# motor_shield.net
KiCad netlist of a schematic drawn in EAGLE
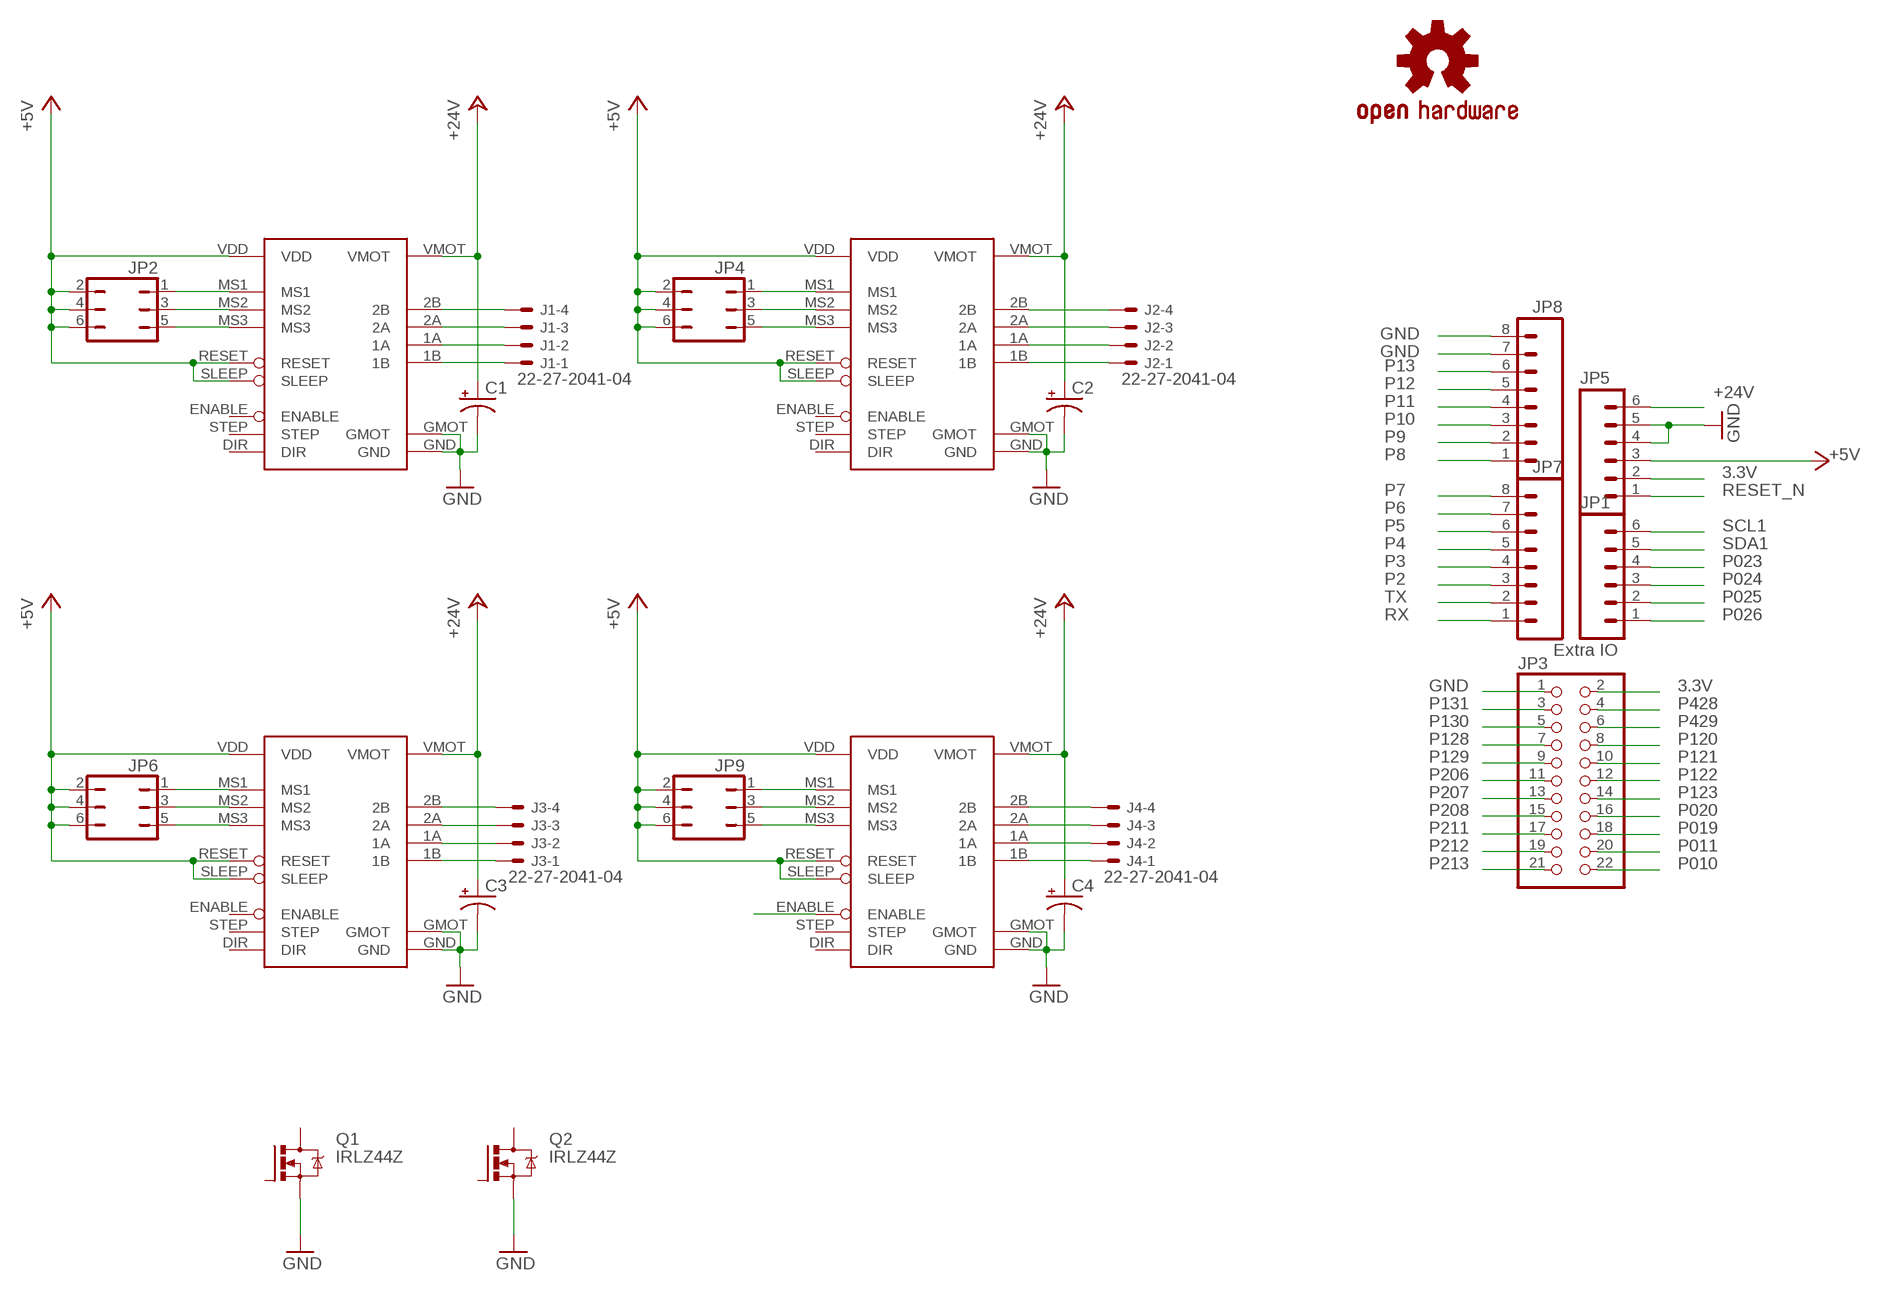
[diagram p0: schematic, sheet 1]

(export (version "E")
  (design (tool "Eeschema 10.0.6"))
  (components
    (comp (ref "C1")
      (value "CAP_POLPTH1")
      (footprint "eagle-import:CPOL-RADIAL-100UF-25V")
      (libsource (lib "eagle-import") (part "CAP_POLPTH1"))
    )
    (comp (ref "C2")
      (value "CAP_POLPTH1")
      (footprint "eagle-import:CPOL-RADIAL-100UF-25V")
      (libsource (lib "eagle-import") (part "CAP_POLPTH1"))
    )
    (comp (ref "C3")
      (value "CAP_POLPTH1")
      (footprint "eagle-import:CPOL-RADIAL-100UF-25V")
      (libsource (lib "eagle-import") (part "CAP_POLPTH1"))
    )
    (comp (ref "C4")
      (value "CAP_POLPTH1")
      (footprint "eagle-import:CPOL-RADIAL-100UF-25V")
      (libsource (lib "eagle-import") (part "CAP_POLPTH1"))
    )
    (comp (ref "J1")
      (value "22-27-2041-04")
      (footprint "eagle-import:6410-04")
      (libsource (lib "eagle-import") (part "22-?-0427-2041"))
    )
    (comp (ref "J2")
      (value "22-27-2041-04")
      (footprint "eagle-import:6410-04")
      (libsource (lib "eagle-import") (part "22-?-0427-2041"))
    )
    (comp (ref "J3")
      (value "22-27-2041-04")
      (footprint "eagle-import:6410-04")
      (libsource (lib "eagle-import") (part "22-?-0427-2041"))
    )
    (comp (ref "J4")
      (value "22-27-2041-04")
      (footprint "eagle-import:6410-04")
      (libsource (lib "eagle-import") (part "22-?-0427-2041"))
    )
    (comp (ref "JP1")
      (value "M06SIP")
      (footprint "eagle-import:1X06")
      (libsource (lib "eagle-import") (part "M06SIP"))
    )
    (comp (ref "JP2")
      (value "JP3Q")
      (footprint "eagle-import:JP3Q")
      (libsource (lib "eagle-import") (part "JP3Q"))
    )
    (comp (ref "JP3")
      (value "PINHD-2X11")
      (footprint "eagle-import:2X11")
      (libsource (lib "eagle-import") (part "PINHD-2X11"))
    )
    (comp (ref "JP4")
      (value "JP3Q")
      (footprint "eagle-import:JP3Q")
      (libsource (lib "eagle-import") (part "JP3Q"))
    )
    (comp (ref "JP5")
      (value "M06SIP")
      (footprint "eagle-import:1X06")
      (libsource (lib "eagle-import") (part "M06SIP"))
    )
    (comp (ref "JP6")
      (value "JP3Q")
      (footprint "eagle-import:JP3Q")
      (libsource (lib "eagle-import") (part "JP3Q"))
    )
    (comp (ref "JP7")
      (value "M08")
      (footprint "eagle-import:1X08")
      (libsource (lib "eagle-import") (part "M08"))
    )
    (comp (ref "JP8")
      (value "M08")
      (footprint "eagle-import:1X08")
      (libsource (lib "eagle-import") (part "M08"))
    )
    (comp (ref "JP9")
      (value "JP3Q")
      (footprint "eagle-import:JP3Q")
      (libsource (lib "eagle-import") (part "JP3Q"))
    )
    (comp (ref "OPENHARDWARE")
      (value "OSHW-LOGOL")
      (footprint "eagle-import:OSHW-LOGO-L")
      (libsource (lib "eagle-import") (part "OSHW-LOGOL"))
    )
    (comp (ref "Q1")
      (value "IRLZ44Z")
      (footprint "eagle-import:TO220BH")
      (libsource (lib "eagle-import") (part "IRLZ44Z"))
    )
    (comp (ref "Q2")
      (value "IRLZ44Z")
      (footprint "eagle-import:TO220BH")
      (libsource (lib "eagle-import") (part "IRLZ44Z"))
    )
    (comp (ref "U$1")
      (value "A4988")
      (footprint "eagle-import:A4988")
      (libsource (lib "eagle-import") (part "A4988"))
    )
    (comp (ref "U$2")
      (value "A4988")
      (footprint "eagle-import:A4988")
      (libsource (lib "eagle-import") (part "A4988"))
    )
    (comp (ref "U$3")
      (value "A4988")
      (footprint "eagle-import:A4988")
      (libsource (lib "eagle-import") (part "A4988"))
    )
    (comp (ref "U$4")
      (value "A4988")
      (footprint "eagle-import:A4988")
      (libsource (lib "eagle-import") (part "A4988"))
    )
  )
  (nets
    (net (code "1") (name "+5V") (class "Default")
      (node (ref "JP2") (pin "2") (pinfunction "2_2") (pintype "passive"))
      (node (ref "JP2") (pin "4") (pinfunction "4_4") (pintype "passive"))
      (node (ref "JP2") (pin "6") (pinfunction "6_6") (pintype "passive"))
      (node (ref "JP4") (pin "2") (pinfunction "2_2") (pintype "passive"))
      (node (ref "JP4") (pin "4") (pinfunction "4_4") (pintype "passive"))
      (node (ref "JP4") (pin "6") (pinfunction "6_6") (pintype "passive"))
      (node (ref "JP5") (pin "3") (pinfunction "3_3") (pintype "passive"))
      (node (ref "JP6") (pin "2") (pinfunction "2_2") (pintype "passive"))
      (node (ref "JP6") (pin "4") (pinfunction "4_4") (pintype "passive"))
      (node (ref "JP6") (pin "6") (pinfunction "6_6") (pintype "passive"))
      (node (ref "JP9") (pin "2") (pinfunction "2_2") (pintype "passive"))
      (node (ref "JP9") (pin "4") (pinfunction "4_4") (pintype "passive"))
      (node (ref "JP9") (pin "6") (pinfunction "6_6") (pintype "passive"))
      (node (ref "U$1") (pin "RESET") (pinfunction "RESET_RESET") (pintype "input"))
      (node (ref "U$1") (pin "SLEEP") (pinfunction "SLEEP_SLEEP") (pintype "input"))
      (node (ref "U$1") (pin "VDD") (pinfunction "VDD_VDD") (pintype "bidirectional"))
      (node (ref "U$2") (pin "RESET") (pinfunction "RESET_RESET") (pintype "input"))
      (node (ref "U$2") (pin "SLEEP") (pinfunction "SLEEP_SLEEP") (pintype "input"))
      (node (ref "U$2") (pin "VDD") (pinfunction "VDD_VDD") (pintype "bidirectional"))
      (node (ref "U$3") (pin "RESET") (pinfunction "RESET_RESET") (pintype "input"))
      (node (ref "U$3") (pin "SLEEP") (pinfunction "SLEEP_SLEEP") (pintype "input"))
      (node (ref "U$3") (pin "VDD") (pinfunction "VDD_VDD") (pintype "bidirectional"))
      (node (ref "U$4") (pin "RESET") (pinfunction "RESET_RESET") (pintype "input"))
      (node (ref "U$4") (pin "SLEEP") (pinfunction "SLEEP_SLEEP") (pintype "input"))
      (node (ref "U$4") (pin "VDD") (pinfunction "VDD_VDD") (pintype "bidirectional"))
    )
    (net (code "2") (name "+24V") (class "Default")
      (node (ref "C1") (pin "1") (pinfunction "+_1") (pintype "passive"))
      (node (ref "C2") (pin "1") (pinfunction "+_1") (pintype "passive"))
      (node (ref "C3") (pin "1") (pinfunction "+_1") (pintype "passive"))
      (node (ref "C4") (pin "1") (pinfunction "+_1") (pintype "passive"))
      (node (ref "JP5") (pin "6") (pinfunction "6_6") (pintype "passive"))
      (node (ref "U$1") (pin "VMOT") (pinfunction "VMOT_VMOT") (pintype "bidirectional"))
      (node (ref "U$2") (pin "VMOT") (pinfunction "VMOT_VMOT") (pintype "bidirectional"))
      (node (ref "U$3") (pin "VMOT") (pinfunction "VMOT_VMOT") (pintype "bidirectional"))
      (node (ref "U$4") (pin "VMOT") (pinfunction "VMOT_VMOT") (pintype "bidirectional"))
    )
    (net (code "3") (name "/3.3V") (class "Default")
      (node (ref "JP3") (pin "2") (pinfunction "2_2") (pintype "passive"))
      (node (ref "JP5") (pin "2") (pinfunction "2_2") (pintype "passive"))
    )
    (net (code "4") (name "/P2") (class "Default")
      (node (ref "JP7") (pin "3") (pinfunction "3_3") (pintype "passive"))
    )
    (net (code "5") (name "/P3") (class "Default")
      (node (ref "JP7") (pin "4") (pinfunction "4_4") (pintype "passive"))
    )
    (net (code "6") (name "/P4") (class "Default")
      (node (ref "JP7") (pin "5") (pinfunction "5_5") (pintype "passive"))
    )
    (net (code "7") (name "/P5") (class "Default")
      (node (ref "JP7") (pin "6") (pinfunction "6_6") (pintype "passive"))
    )
    (net (code "8") (name "/P6") (class "Default")
      (node (ref "JP7") (pin "7") (pinfunction "7_7") (pintype "passive"))
    )
    (net (code "9") (name "/P7") (class "Default")
      (node (ref "JP7") (pin "8") (pinfunction "8_8") (pintype "passive"))
    )
    (net (code "10") (name "/P8") (class "Default")
      (node (ref "JP8") (pin "1") (pinfunction "1_1") (pintype "passive"))
    )
    (net (code "11") (name "/P9") (class "Default")
      (node (ref "JP8") (pin "2") (pinfunction "2_2") (pintype "passive"))
    )
    (net (code "12") (name "/P010") (class "Default")
      (node (ref "JP3") (pin "22") (pinfunction "22_22") (pintype "passive"))
    )
    (net (code "13") (name "/P10") (class "Default")
      (node (ref "JP8") (pin "3") (pinfunction "3_3") (pintype "passive"))
    )
    (net (code "14") (name "/P11") (class "Default")
      (node (ref "JP8") (pin "4") (pinfunction "4_4") (pintype "passive"))
    )
    (net (code "15") (name "/P011") (class "Default")
      (node (ref "JP3") (pin "20") (pinfunction "20_20") (pintype "passive"))
    )
    (net (code "16") (name "/P12") (class "Default")
      (node (ref "JP8") (pin "5") (pinfunction "5_5") (pintype "passive"))
    )
    (net (code "17") (name "/P13") (class "Default")
      (node (ref "JP8") (pin "6") (pinfunction "6_6") (pintype "passive"))
    )
    (net (code "18") (name "/P019") (class "Default")
      (node (ref "JP3") (pin "18") (pinfunction "18_18") (pintype "passive"))
    )
    (net (code "19") (name "/P020") (class "Default")
      (node (ref "JP3") (pin "16") (pinfunction "16_16") (pintype "passive"))
    )
    (net (code "20") (name "/P023") (class "Default")
      (node (ref "JP1") (pin "4") (pinfunction "4_4") (pintype "passive"))
    )
    (net (code "21") (name "/P024") (class "Default")
      (node (ref "JP1") (pin "3") (pinfunction "3_3") (pintype "passive"))
    )
    (net (code "22") (name "/P025") (class "Default")
      (node (ref "JP1") (pin "2") (pinfunction "2_2") (pintype "passive"))
    )
    (net (code "23") (name "/P026") (class "Default")
      (node (ref "JP1") (pin "1") (pinfunction "1_1") (pintype "passive"))
      (node (ref "U$4") (pin "ENABLE") (pinfunction "ENABLE_ENABLE") (pintype "input"))
    )
    (net (code "24") (name "/P120") (class "Default")
      (node (ref "JP3") (pin "8") (pinfunction "8_8") (pintype "passive"))
    )
    (net (code "25") (name "/P121") (class "Default")
      (node (ref "JP3") (pin "10") (pinfunction "10_10") (pintype "passive"))
    )
    (net (code "26") (name "/P122") (class "Default")
      (node (ref "JP3") (pin "12") (pinfunction "12_12") (pintype "passive"))
    )
    (net (code "27") (name "/P123") (class "Default")
      (node (ref "JP3") (pin "14") (pinfunction "14_14") (pintype "passive"))
    )
    (net (code "28") (name "/P128") (class "Default")
      (node (ref "JP3") (pin "7") (pinfunction "7_7") (pintype "passive"))
    )
    (net (code "29") (name "/P129") (class "Default")
      (node (ref "JP3") (pin "9") (pinfunction "9_9") (pintype "passive"))
    )
    (net (code "30") (name "/P130") (class "Default")
      (node (ref "JP3") (pin "5") (pinfunction "5_5") (pintype "passive"))
    )
    (net (code "31") (name "/P131") (class "Default")
      (node (ref "JP3") (pin "3") (pinfunction "3_3") (pintype "passive"))
    )
    (net (code "32") (name "/P206") (class "Default")
      (node (ref "JP3") (pin "11") (pinfunction "11_11") (pintype "passive"))
    )
    (net (code "33") (name "/P207") (class "Default")
      (node (ref "JP3") (pin "13") (pinfunction "13_13") (pintype "passive"))
    )
    (net (code "34") (name "/P208") (class "Default")
      (node (ref "JP3") (pin "15") (pinfunction "15_15") (pintype "passive"))
    )
    (net (code "35") (name "/P211") (class "Default")
      (node (ref "JP3") (pin "17") (pinfunction "17_17") (pintype "passive"))
    )
    (net (code "36") (name "/P212") (class "Default")
      (node (ref "JP3") (pin "19") (pinfunction "19_19") (pintype "passive"))
    )
    (net (code "37") (name "/P213") (class "Default")
      (node (ref "JP3") (pin "21") (pinfunction "21_21") (pintype "passive"))
    )
    (net (code "38") (name "/P428") (class "Default")
      (node (ref "JP3") (pin "4") (pinfunction "4_4") (pintype "passive"))
    )
    (net (code "39") (name "/P429") (class "Default")
      (node (ref "JP3") (pin "6") (pinfunction "6_6") (pintype "passive"))
    )
    (net (code "40") (name "/RESET_N") (class "Default")
      (node (ref "JP5") (pin "1") (pinfunction "1_1") (pintype "passive"))
    )
    (net (code "41") (name "/RX") (class "Default")
      (node (ref "JP7") (pin "1") (pinfunction "1_1") (pintype "passive"))
    )
    (net (code "42") (name "/SCL1") (class "Default")
      (node (ref "JP1") (pin "6") (pinfunction "6_6") (pintype "passive"))
    )
    (net (code "43") (name "/SDA1") (class "Default")
      (node (ref "JP1") (pin "5") (pinfunction "5_5") (pintype "passive"))
    )
    (net (code "44") (name "/TX") (class "Default")
      (node (ref "JP7") (pin "2") (pinfunction "2_2") (pintype "passive"))
    )
    (net (code "45") (name "GND") (class "Default")
      (node (ref "C1") (pin "2") (pinfunction "-_2") (pintype "passive"))
      (node (ref "C2") (pin "2") (pinfunction "-_2") (pintype "passive"))
      (node (ref "C3") (pin "2") (pinfunction "-_2") (pintype "passive"))
      (node (ref "C4") (pin "2") (pinfunction "-_2") (pintype "passive"))
      (node (ref "JP3") (pin "1") (pinfunction "1_1") (pintype "passive"))
      (node (ref "JP5") (pin "4") (pinfunction "4_4") (pintype "passive"))
      (node (ref "JP5") (pin "5") (pinfunction "5_5") (pintype "passive"))
      (node (ref "JP8") (pin "7") (pinfunction "7_7") (pintype "passive"))
      (node (ref "JP8") (pin "8") (pinfunction "8_8") (pintype "passive"))
      (node (ref "Q1") (pin "S") (pinfunction "S_S") (pintype "passive"))
      (node (ref "Q2") (pin "S") (pinfunction "S_S") (pintype "passive"))
      (node (ref "U$1") (pin "GMOT") (pinfunction "GMOT_GMOT") (pintype "bidirectional"))
      (node (ref "U$1") (pin "GND") (pinfunction "GND_GND") (pintype "bidirectional"))
      (node (ref "U$2") (pin "GMOT") (pinfunction "GMOT_GMOT") (pintype "bidirectional"))
      (node (ref "U$2") (pin "GND") (pinfunction "GND_GND") (pintype "bidirectional"))
      (node (ref "U$3") (pin "GMOT") (pinfunction "GMOT_GMOT") (pintype "bidirectional"))
      (node (ref "U$3") (pin "GND") (pinfunction "GND_GND") (pintype "bidirectional"))
      (node (ref "U$4") (pin "GMOT") (pinfunction "GMOT_GMOT") (pintype "bidirectional"))
      (node (ref "U$4") (pin "GND") (pinfunction "GND_GND") (pintype "bidirectional"))
    )
    (net (code "46") (name "Net-(J1A-S)") (class "Default")
      (node (ref "J1") (pin "1") (pinfunction "S_1") (pintype "passive"))
      (node (ref "U$1") (pin "1B") (pinfunction "1B_1B") (pintype "output"))
    )
    (net (code "47") (name "Net-(J1B-S)") (class "Default")
      (node (ref "J1") (pin "2") (pinfunction "S_2") (pintype "passive"))
      (node (ref "U$1") (pin "1A") (pinfunction "1A_1A") (pintype "output"))
    )
    (net (code "48") (name "Net-(J1C-S)") (class "Default")
      (node (ref "J1") (pin "3") (pinfunction "S_3") (pintype "passive"))
      (node (ref "U$1") (pin "2A") (pinfunction "2A_2A") (pintype "output"))
    )
    (net (code "49") (name "Net-(J1D-S)") (class "Default")
      (node (ref "J1") (pin "4") (pinfunction "S_4") (pintype "passive"))
      (node (ref "U$1") (pin "2B") (pinfunction "2B_2B") (pintype "output"))
    )
    (net (code "50") (name "Net-(J2A-S)") (class "Default")
      (node (ref "J2") (pin "1") (pinfunction "S_1") (pintype "passive"))
      (node (ref "U$2") (pin "1B") (pinfunction "1B_1B") (pintype "output"))
    )
    (net (code "51") (name "Net-(J2B-S)") (class "Default")
      (node (ref "J2") (pin "2") (pinfunction "S_2") (pintype "passive"))
      (node (ref "U$2") (pin "1A") (pinfunction "1A_1A") (pintype "output"))
    )
    (net (code "52") (name "Net-(J2C-S)") (class "Default")
      (node (ref "J2") (pin "3") (pinfunction "S_3") (pintype "passive"))
      (node (ref "U$2") (pin "2A") (pinfunction "2A_2A") (pintype "output"))
    )
    (net (code "53") (name "Net-(J2D-S)") (class "Default")
      (node (ref "J2") (pin "4") (pinfunction "S_4") (pintype "passive"))
      (node (ref "U$2") (pin "2B") (pinfunction "2B_2B") (pintype "output"))
    )
    (net (code "54") (name "Net-(J3A-S)") (class "Default")
      (node (ref "J3") (pin "1") (pinfunction "S_1") (pintype "passive"))
      (node (ref "U$3") (pin "1B") (pinfunction "1B_1B") (pintype "output"))
    )
    (net (code "55") (name "Net-(J3B-S)") (class "Default")
      (node (ref "J3") (pin "2") (pinfunction "S_2") (pintype "passive"))
      (node (ref "U$3") (pin "1A") (pinfunction "1A_1A") (pintype "output"))
    )
    (net (code "56") (name "Net-(J3C-S)") (class "Default")
      (node (ref "J3") (pin "3") (pinfunction "S_3") (pintype "passive"))
      (node (ref "U$3") (pin "2A") (pinfunction "2A_2A") (pintype "output"))
    )
    (net (code "57") (name "Net-(J3D-S)") (class "Default")
      (node (ref "J3") (pin "4") (pinfunction "S_4") (pintype "passive"))
      (node (ref "U$3") (pin "2B") (pinfunction "2B_2B") (pintype "output"))
    )
    (net (code "58") (name "Net-(J4A-S)") (class "Default")
      (node (ref "J4") (pin "1") (pinfunction "S_1") (pintype "passive"))
      (node (ref "U$4") (pin "1B") (pinfunction "1B_1B") (pintype "output"))
    )
    (net (code "59") (name "Net-(J4B-S)") (class "Default")
      (node (ref "J4") (pin "2") (pinfunction "S_2") (pintype "passive"))
      (node (ref "U$4") (pin "1A") (pinfunction "1A_1A") (pintype "output"))
    )
    (net (code "60") (name "Net-(J4C-S)") (class "Default")
      (node (ref "J4") (pin "3") (pinfunction "S_3") (pintype "passive"))
      (node (ref "U$4") (pin "2A") (pinfunction "2A_2A") (pintype "output"))
    )
    (net (code "61") (name "Net-(J4D-S)") (class "Default")
      (node (ref "J4") (pin "4") (pinfunction "S_4") (pintype "passive"))
      (node (ref "U$4") (pin "2B") (pinfunction "2B_2B") (pintype "output"))
    )
    (net (code "62") (name "Net-(JP2-Pad1)") (class "Default")
      (node (ref "JP2") (pin "1") (pinfunction "1_1") (pintype "passive"))
      (node (ref "U$1") (pin "MS1") (pinfunction "MS1_MS1") (pintype "bidirectional"))
    )
    (net (code "63") (name "Net-(JP2-Pad3)") (class "Default")
      (node (ref "JP2") (pin "3") (pinfunction "3_3") (pintype "passive"))
      (node (ref "U$1") (pin "MS2") (pinfunction "MS2_MS2") (pintype "bidirectional"))
    )
    (net (code "64") (name "Net-(JP2-Pad5)") (class "Default")
      (node (ref "JP2") (pin "5") (pinfunction "5_5") (pintype "passive"))
      (node (ref "U$1") (pin "MS3") (pinfunction "MS3_MS3") (pintype "bidirectional"))
    )
    (net (code "65") (name "Net-(JP4-Pad1)") (class "Default")
      (node (ref "JP4") (pin "1") (pinfunction "1_1") (pintype "passive"))
      (node (ref "U$2") (pin "MS1") (pinfunction "MS1_MS1") (pintype "bidirectional"))
    )
    (net (code "66") (name "Net-(JP4-Pad3)") (class "Default")
      (node (ref "JP4") (pin "3") (pinfunction "3_3") (pintype "passive"))
      (node (ref "U$2") (pin "MS2") (pinfunction "MS2_MS2") (pintype "bidirectional"))
    )
    (net (code "67") (name "Net-(JP4-Pad5)") (class "Default")
      (node (ref "JP4") (pin "5") (pinfunction "5_5") (pintype "passive"))
      (node (ref "U$2") (pin "MS3") (pinfunction "MS3_MS3") (pintype "bidirectional"))
    )
    (net (code "68") (name "Net-(JP6-Pad1)") (class "Default")
      (node (ref "JP6") (pin "1") (pinfunction "1_1") (pintype "passive"))
      (node (ref "U$3") (pin "MS1") (pinfunction "MS1_MS1") (pintype "bidirectional"))
    )
    (net (code "69") (name "Net-(JP6-Pad3)") (class "Default")
      (node (ref "JP6") (pin "3") (pinfunction "3_3") (pintype "passive"))
      (node (ref "U$3") (pin "MS2") (pinfunction "MS2_MS2") (pintype "bidirectional"))
    )
    (net (code "70") (name "Net-(JP6-Pad5)") (class "Default")
      (node (ref "JP6") (pin "5") (pinfunction "5_5") (pintype "passive"))
      (node (ref "U$3") (pin "MS3") (pinfunction "MS3_MS3") (pintype "bidirectional"))
    )
    (net (code "71") (name "Net-(JP9-Pad1)") (class "Default")
      (node (ref "JP9") (pin "1") (pinfunction "1_1") (pintype "passive"))
      (node (ref "U$4") (pin "MS1") (pinfunction "MS1_MS1") (pintype "bidirectional"))
    )
    (net (code "72") (name "Net-(JP9-Pad3)") (class "Default")
      (node (ref "JP9") (pin "3") (pinfunction "3_3") (pintype "passive"))
      (node (ref "U$4") (pin "MS2") (pinfunction "MS2_MS2") (pintype "bidirectional"))
    )
    (net (code "73") (name "Net-(JP9-Pad5)") (class "Default")
      (node (ref "JP9") (pin "5") (pinfunction "5_5") (pintype "passive"))
      (node (ref "U$4") (pin "MS3") (pinfunction "MS3_MS3") (pintype "bidirectional"))
    )
    (net (code "74") (name "unconnected-(Q1-PadD)") (class "Default")
      (node (ref "Q1") (pin "D") (pinfunction "D_D") (pintype "passive"))
    )
    (net (code "75") (name "unconnected-(Q1-PadG)") (class "Default")
      (node (ref "Q1") (pin "G") (pinfunction "G_G") (pintype "passive"))
    )
    (net (code "76") (name "unconnected-(Q2-PadD)") (class "Default")
      (node (ref "Q2") (pin "D") (pinfunction "D_D") (pintype "passive"))
    )
    (net (code "77") (name "unconnected-(Q2-PadG)") (class "Default")
      (node (ref "Q2") (pin "G") (pinfunction "G_G") (pintype "passive"))
    )
    (net (code "78") (name "unconnected-(U$1-PadDIR)") (class "Default")
      (node (ref "U$1") (pin "DIR") (pinfunction "DIR_DIR") (pintype "input"))
    )
    (net (code "79") (name "unconnected-(U$1-PadENABLE)") (class "Default")
      (node (ref "U$1") (pin "ENABLE") (pinfunction "ENABLE_ENABLE") (pintype "input"))
    )
    (net (code "80") (name "unconnected-(U$1-PadSTEP)") (class "Default")
      (node (ref "U$1") (pin "STEP") (pinfunction "STEP_STEP") (pintype "input"))
    )
    (net (code "81") (name "unconnected-(U$2-PadDIR)") (class "Default")
      (node (ref "U$2") (pin "DIR") (pinfunction "DIR_DIR") (pintype "input"))
    )
    (net (code "82") (name "unconnected-(U$2-PadENABLE)") (class "Default")
      (node (ref "U$2") (pin "ENABLE") (pinfunction "ENABLE_ENABLE") (pintype "input"))
    )
    (net (code "83") (name "unconnected-(U$2-PadSTEP)") (class "Default")
      (node (ref "U$2") (pin "STEP") (pinfunction "STEP_STEP") (pintype "input"))
    )
    (net (code "84") (name "unconnected-(U$3-PadDIR)") (class "Default")
      (node (ref "U$3") (pin "DIR") (pinfunction "DIR_DIR") (pintype "input"))
    )
    (net (code "85") (name "unconnected-(U$3-PadENABLE)") (class "Default")
      (node (ref "U$3") (pin "ENABLE") (pinfunction "ENABLE_ENABLE") (pintype "input"))
    )
    (net (code "86") (name "unconnected-(U$3-PadSTEP)") (class "Default")
      (node (ref "U$3") (pin "STEP") (pinfunction "STEP_STEP") (pintype "input"))
    )
    (net (code "87") (name "unconnected-(U$4-PadDIR)") (class "Default")
      (node (ref "U$4") (pin "DIR") (pinfunction "DIR_DIR") (pintype "input"))
    )
    (net (code "88") (name "unconnected-(U$4-PadSTEP)") (class "Default")
      (node (ref "U$4") (pin "STEP") (pinfunction "STEP_STEP") (pintype "input"))
    )
  )
)
